# SCH_Project2_2025-11-09.net
KiCad netlist of a schematic drawn in EasyEDA
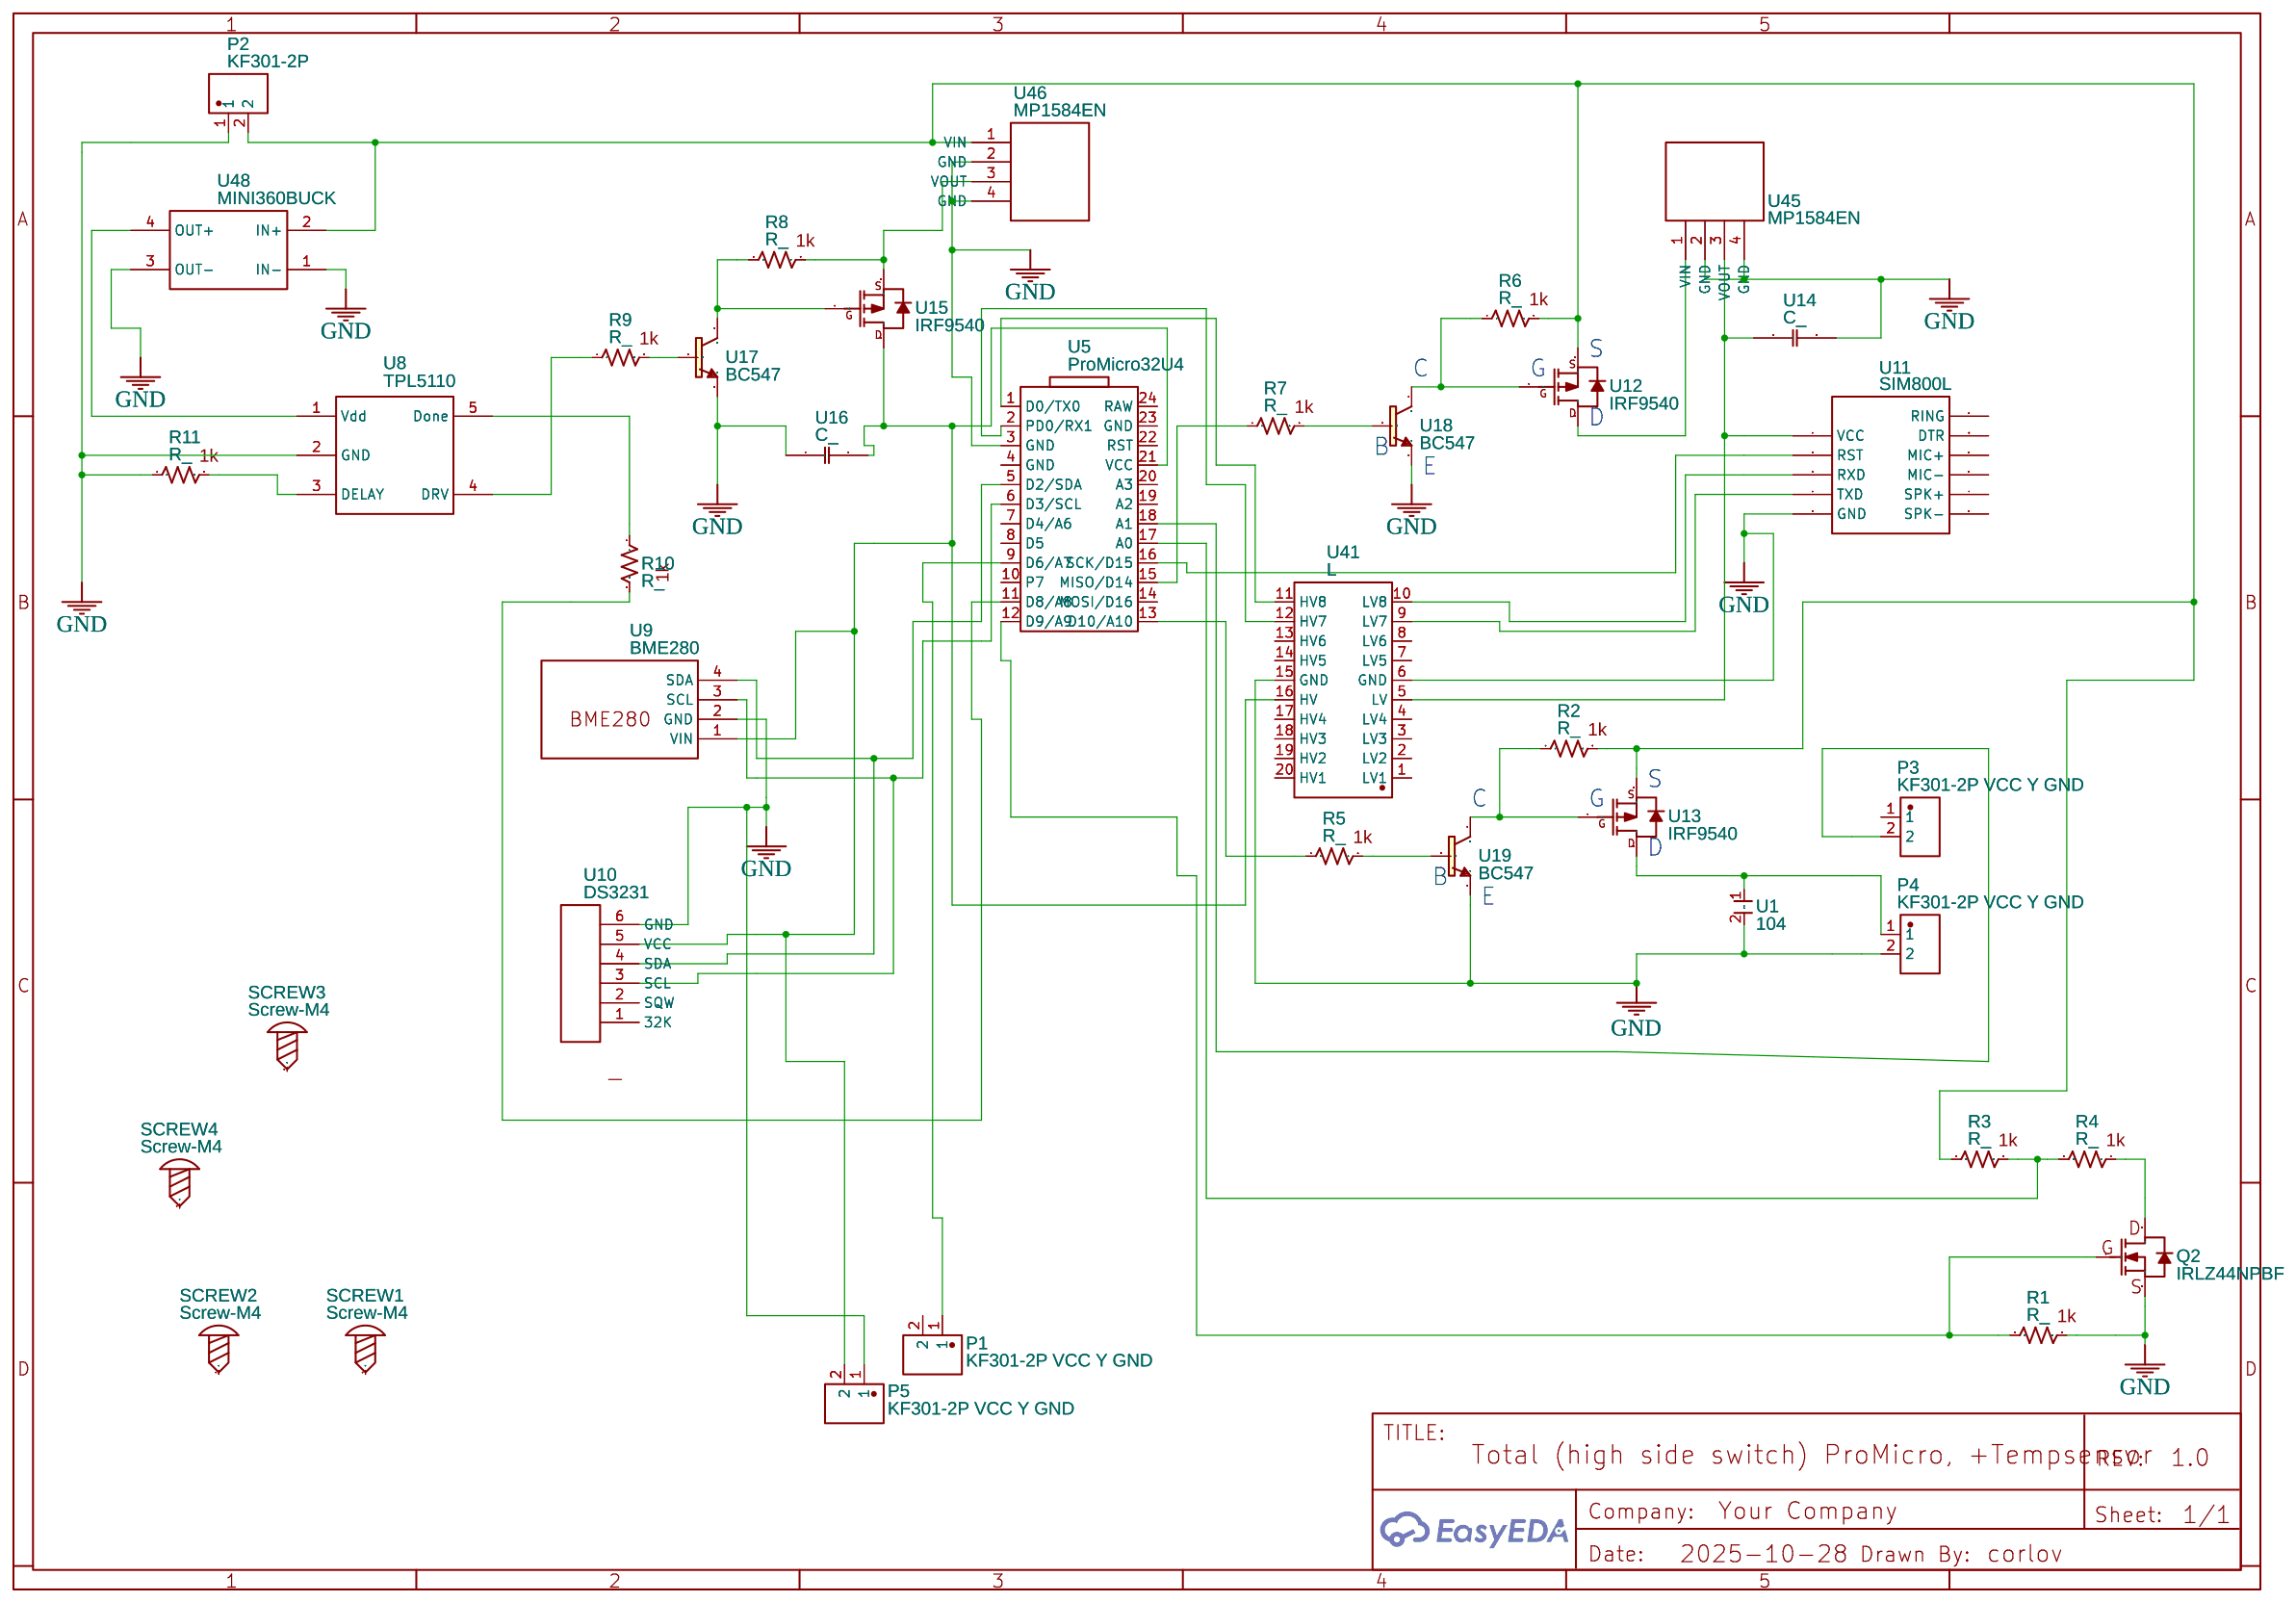
[diagram p0: schematic sheet]

(export (version "E")
  (design (tool "Eeschema 10.0.6"))
  (components
    (comp (ref "P1")
      (value "KF301-2P VCC Y GND")
      (fields (field (name "Manufacturer Part") "KF301-2P接线端子"))
      (libsource (lib "") (part "KF301-2P VCC Y GND_1"))
    )
    (comp (ref "P2")
      (value "KF301-2P")
      (fields (field (name "Manufacturer Part") "KF301-2P接线端子"))
      (libsource (lib "") (part "KF301-2P VCC Y GND_2"))
    )
    (comp (ref "P3")
      (value "KF301-2P VCC Y GND")
      (fields (field (name "Manufacturer Part") "KF301-2P接线端子"))
      (libsource (lib "") (part "KF301-2P VCC Y GND"))
    )
    (comp (ref "P4")
      (value "KF301-2P VCC Y GND")
      (fields (field (name "Manufacturer Part") "KF301-2P接线端子"))
      (libsource (lib "") (part "KF301-2P VCC Y GND"))
    )
    (comp (ref "P5")
      (value "KF301-2P VCC Y GND")
      (fields (field (name "Manufacturer Part") "KF301-2P接线端子"))
      (libsource (lib "") (part "KF301-2P VCC Y GND_1"))
    )
    (comp (ref "Q2")
      (value "IRLZ44NPBF")
      (fields (field (name "Manufacturer") "Infineon(英飞凌)"))
      (libsource (lib "") (part "IRLZ44NPBF"))
    )
    (comp (ref "R1") (value "R_") (libsource (lib "") (part "R_")))
    (comp (ref "R2") (value "R_") (libsource (lib "") (part "R_")))
    (comp (ref "R3") (value "R_") (libsource (lib "") (part "R_")))
    (comp (ref "R4") (value "R_") (libsource (lib "") (part "R_")))
    (comp (ref "R5") (value "R_") (libsource (lib "") (part "R_")))
    (comp (ref "R6") (value "R_") (libsource (lib "") (part "R_")))
    (comp (ref "R7") (value "R_") (libsource (lib "") (part "R_")))
    (comp (ref "R8") (value "R_") (libsource (lib "") (part "R_")))
    (comp (ref "R9") (value "R_") (libsource (lib "") (part "R_")))
    (comp (ref "R10") (value "R_") (libsource (lib "") (part "R__1")))
    (comp (ref "R11") (value "R_") (libsource (lib "") (part "R_")))
    (comp (ref "SCREW1") (value "Screw-M4") (libsource (lib "") (part "Screw-M4")))
    (comp (ref "SCREW2") (value "Screw-M4") (libsource (lib "") (part "Screw-M4")))
    (comp (ref "SCREW3") (value "Screw-M4") (libsource (lib "") (part "Screw-M4")))
    (comp (ref "SCREW4") (value "Screw-M4") (libsource (lib "") (part "Screw-M4")))
    (comp (ref "U1")
      (value "104")
      (fields (field (name "Manufacturer") "Fe"))
      (libsource (lib "") (part "104"))
    )
    (comp (ref "U5")
      (value "ProMicro32U4")
      (fields (field (name "Manufacturer Part") "generic"))
      (libsource (lib "") (part "ProMicro32U4"))
    )
    (comp (ref "U8")
      (value "TPL5110")
      (fields (field (name "Manufacturer Part") "3435"))
      (libsource (lib "") (part "ADAFRUIT TPL5110 BREAKOUT"))
    )
    (comp (ref "U9") (value "BME280") (libsource (lib "") (part "BME280")))
    (comp (ref "U10") (value "DS3231") (libsource (lib "") (part "DS3231 upright")))
    (comp (ref "U11") (value "SIM800L") (libsource (lib "") (part "SIM800L")))
    (comp (ref "U12") (value "IRF9540") (libsource (lib "") (part "IRF9540")))
    (comp (ref "U13") (value "IRF9540") (libsource (lib "") (part "IRF9540")))
    (comp (ref "U14") (value "C_") (libsource (lib "") (part "C_")))
    (comp (ref "U15") (value "IRF9540") (libsource (lib "") (part "IRF9540")))
    (comp (ref "U16") (value "C_") (libsource (lib "") (part "C_")))
    (comp (ref "U17") (value "BC547") (libsource (lib "") (part "BC547")))
    (comp (ref "U18") (value "BC547") (libsource (lib "") (part "BC547")))
    (comp (ref "U19") (value "BC547") (libsource (lib "") (part "BC547")))
    (comp (ref "U41")
      (value "L")
      (fields (field (name "Manufacturer Part") "Level Converter 8"))
      (libsource (lib "") (part "LEVEL CONVERTER 8"))
    )
    (comp (ref "U45") (value "MP1584EN") (libsource (lib "") (part "MP1584EN_1")))
    (comp (ref "U46") (value "MP1584EN") (libsource (lib "") (part "MP1584EN")))
    (comp (ref "U48")
      (value "MINI360BUCK")
      (fields (field (name "Manufacturer Part") "Mini360"))
      (libsource (lib "") (part "MINI360BUCK"))
    )
  )
  (nets
    (net (code "1") (name "GND") (class "Default")
      (node (ref "P2") (pin "1") (pinfunction "1_1") (pintype "unspecified"))
      (node (ref "P4") (pin "2") (pinfunction "2_2") (pintype "unspecified"))
      (node (ref "P5") (pin "1") (pinfunction "1_1") (pintype "unspecified"))
      (node (ref "Q2") (pin "3") (pinfunction "S_3") (pintype "unspecified"))
      (node (ref "R1") (pin "2") (pinfunction "2_2") (pintype "unspecified"))
      (node (ref "R11") (pin "1") (pinfunction "1_1") (pintype "unspecified"))
      (node (ref "U1") (pin "2") (pinfunction "2_2") (pintype "unspecified"))
      (node (ref "U10") (pin "6") (pinfunction "GND_6") (pintype "unspecified"))
      (node (ref "U11") (pin "5") (pinfunction "GND_5") (pintype "unspecified"))
      (node (ref "U14") (pin "2") (pinfunction "2_2") (pintype "unspecified"))
      (node (ref "U16") (pin "1") (pinfunction "1_1") (pintype "unspecified"))
      (node (ref "U17") (pin "3") (pinfunction "E_3") (pintype "unspecified"))
      (node (ref "U18") (pin "3") (pinfunction "E_3") (pintype "unspecified"))
      (node (ref "U19") (pin "3") (pinfunction "E_3") (pintype "unspecified"))
      (node (ref "U41") (pin "15") (pinfunction "GND_15") (pintype "unspecified"))
      (node (ref "U41") (pin "6") (pinfunction "GND_6") (pintype "unspecified"))
      (node (ref "U45") (pin "2") (pinfunction "GND_2") (pintype "unspecified"))
      (node (ref "U45") (pin "4") (pinfunction "GND_4") (pintype "unspecified"))
      (node (ref "U46") (pin "2") (pinfunction "GND_2") (pintype "unspecified"))
      (node (ref "U46") (pin "4") (pinfunction "GND_4") (pintype "unspecified"))
      (node (ref "U48") (pin "1") (pinfunction "IN-_1") (pintype "unspecified"))
      (node (ref "U48") (pin "3") (pinfunction "OUT-_3") (pintype "unspecified"))
      (node (ref "U5") (pin "3") (pinfunction "GND_3") (pintype "unspecified"))
      (node (ref "U8") (pin "2") (pinfunction "GND_2") (pintype "unspecified"))
      (node (ref "U9") (pin "2") (pinfunction "GND_2") (pintype "unspecified"))
    )
    (net (code "2") (name "Net-(Q2-D)") (class "Default")
      (node (ref "Q2") (pin "2") (pinfunction "D_2") (pintype "unspecified"))
      (node (ref "R4") (pin "2") (pinfunction "2_2") (pintype "unspecified"))
    )
    (net (code "3") (name "Net-(Q2-G)") (class "Default")
      (node (ref "Q2") (pin "1") (pinfunction "G_1") (pintype "unspecified"))
      (node (ref "R1") (pin "1") (pinfunction "1_1") (pintype "unspecified"))
      (node (ref "U5") (pin "12") (pinfunction "D9/A9_12") (pintype "unspecified"))
    )
    (net (code "4") (name "Net-(U5-A0)") (class "Default")
      (node (ref "R3") (pin "2") (pinfunction "2_2") (pintype "unspecified"))
      (node (ref "R4") (pin "1") (pinfunction "1_1") (pintype "unspecified"))
      (node (ref "U5") (pin "17") (pinfunction "A0_17") (pintype "unspecified"))
    )
    (net (code "5") (name "Net-(U5-A1)") (class "Default")
      (node (ref "P3") (pin "2") (pinfunction "2_2") (pintype "unspecified"))
      (node (ref "U5") (pin "18") (pinfunction "A1_18") (pintype "unspecified"))
    )
    (net (code "6") (name "Net-(U5-D6{slash}A7)") (class "Default")
      (node (ref "P1") (pin "1") (pinfunction "1_1") (pintype "unspecified"))
      (node (ref "U5") (pin "9") (pinfunction "D6/A7_9") (pintype "unspecified"))
    )
    (net (code "7") (name "Net-(U5-D8{slash}A8)") (class "Default")
      (node (ref "R10") (pin "2") (pinfunction "2_2") (pintype "unspecified"))
      (node (ref "U5") (pin "11") (pinfunction "D8/A8_11") (pintype "unspecified"))
    )
    (net (code "8") (name "Net-(U5-D10{slash}A10)") (class "Default")
      (node (ref "R5") (pin "1") (pinfunction "1_1") (pintype "unspecified"))
      (node (ref "U5") (pin "13") (pinfunction "D10/A10_13") (pintype "unspecified"))
    )
    (net (code "9") (name "Net-(U5-MISO{slash}D14)") (class "Default")
      (node (ref "R7") (pin "1") (pinfunction "1_1") (pintype "unspecified"))
      (node (ref "U5") (pin "15") (pinfunction "MISO/D14_15") (pintype "unspecified"))
    )
    (net (code "10") (name "Net-(U8-DELAY)") (class "Default")
      (node (ref "R11") (pin "2") (pinfunction "2_2") (pintype "unspecified"))
      (node (ref "U8") (pin "3") (pinfunction "DELAY_3") (pintype "unspecified"))
    )
    (net (code "11") (name "Net-(U8-DRV)") (class "Default")
      (node (ref "R9") (pin "1") (pinfunction "1_1") (pintype "unspecified"))
      (node (ref "U8") (pin "4") (pinfunction "DRV_4") (pintype "unspecified"))
    )
    (net (code "12") (name "Net-(U8-Done)") (class "Default")
      (node (ref "R10") (pin "1") (pinfunction "1_1") (pintype "unspecified"))
      (node (ref "U8") (pin "5") (pinfunction "Done_5") (pintype "unspecified"))
    )
    (net (code "13") (name "Net-(U10-SCL)") (class "Default")
      (node (ref "U10") (pin "3") (pinfunction "SCL_3") (pintype "unspecified"))
      (node (ref "U5") (pin "6") (pinfunction "D3/SCL_6") (pintype "unspecified"))
      (node (ref "U9") (pin "3") (pinfunction "SCL_3") (pintype "unspecified"))
    )
    (net (code "14") (name "Net-(U10-SDA)") (class "Default")
      (node (ref "U10") (pin "4") (pinfunction "SDA_4") (pintype "unspecified"))
      (node (ref "U5") (pin "5") (pinfunction "D2/SDA_5") (pintype "unspecified"))
      (node (ref "U9") (pin "4") (pinfunction "SDA_4") (pintype "unspecified"))
    )
    (net (code "15") (name "Net-(U10-VCC)") (class "Default")
      (node (ref "P5") (pin "2") (pinfunction "2_2") (pintype "unspecified"))
      (node (ref "U10") (pin "5") (pinfunction "VCC_5") (pintype "unspecified"))
      (node (ref "U15") (pin "2") (pinfunction "D_2") (pintype "unspecified"))
      (node (ref "U16") (pin "2") (pinfunction "2_2") (pintype "unspecified"))
      (node (ref "U41") (pin "16") (pinfunction "HV_16") (pintype "unspecified"))
      (node (ref "U5") (pin "21") (pinfunction "VCC_21") (pintype "unspecified"))
      (node (ref "U9") (pin "1") (pinfunction "VIN_1") (pintype "unspecified"))
    )
    (net (code "16") (name "Net-(U11-RST)") (class "Default")
      (node (ref "U11") (pin "2") (pinfunction "RST_2") (pintype "unspecified"))
      (node (ref "U5") (pin "16") (pinfunction "SCK/D15_16") (pintype "unspecified"))
    )
    (net (code "17") (name "Net-(U11-RXD)") (class "Default")
      (node (ref "U11") (pin "3") (pinfunction "RXD_3") (pintype "unspecified"))
      (node (ref "U41") (pin "10") (pinfunction "LV8_10") (pintype "unspecified"))
    )
    (net (code "18") (name "Net-(U11-TXD)") (class "Default")
      (node (ref "U11") (pin "4") (pinfunction "TXD_4") (pintype "unspecified"))
      (node (ref "U41") (pin "9") (pinfunction "LV7_9") (pintype "unspecified"))
    )
    (net (code "19") (name "Net-(U11-VCC)") (class "Default")
      (node (ref "U11") (pin "1") (pinfunction "VCC_1") (pintype "unspecified"))
      (node (ref "U14") (pin "1") (pinfunction "1_1") (pintype "unspecified"))
      (node (ref "U41") (pin "5") (pinfunction "LV_5") (pintype "unspecified"))
      (node (ref "U45") (pin "3") (pinfunction "VOUT_3") (pintype "unspecified"))
    )
    (net (code "20") (name "Net-(U12-D)") (class "Default")
      (node (ref "U12") (pin "2") (pinfunction "D_2") (pintype "unspecified"))
      (node (ref "U45") (pin "1") (pinfunction "VIN_1") (pintype "unspecified"))
    )
    (net (code "21") (name "Net-(U12-G)") (class "Default")
      (node (ref "R6") (pin "1") (pinfunction "1_1") (pintype "unspecified"))
      (node (ref "U12") (pin "1") (pinfunction "G_1") (pintype "unspecified"))
      (node (ref "U18") (pin "1") (pinfunction "C_1") (pintype "unspecified"))
    )
    (net (code "22") (name "Net-(U12-S)") (class "Default")
      (node (ref "P2") (pin "2") (pinfunction "2_2") (pintype "unspecified"))
      (node (ref "R2") (pin "2") (pinfunction "2_2") (pintype "unspecified"))
      (node (ref "R3") (pin "1") (pinfunction "1_1") (pintype "unspecified"))
      (node (ref "R6") (pin "2") (pinfunction "2_2") (pintype "unspecified"))
      (node (ref "U12") (pin "3") (pinfunction "S_3") (pintype "unspecified"))
      (node (ref "U13") (pin "3") (pinfunction "S_3") (pintype "unspecified"))
      (node (ref "U46") (pin "1") (pinfunction "VIN_1") (pintype "unspecified"))
      (node (ref "U48") (pin "2") (pinfunction "IN+_2") (pintype "unspecified"))
    )
    (net (code "23") (name "Net-(U13-D)") (class "Default")
      (node (ref "P4") (pin "1") (pinfunction "1_1") (pintype "unspecified"))
      (node (ref "U1") (pin "1") (pinfunction "1_1") (pintype "unspecified"))
      (node (ref "U13") (pin "2") (pinfunction "D_2") (pintype "unspecified"))
    )
    (net (code "24") (name "Net-(U13-G)") (class "Default")
      (node (ref "R2") (pin "1") (pinfunction "1_1") (pintype "unspecified"))
      (node (ref "U13") (pin "1") (pinfunction "G_1") (pintype "unspecified"))
      (node (ref "U19") (pin "1") (pinfunction "C_1") (pintype "unspecified"))
    )
    (net (code "25") (name "Net-(U15-G)") (class "Default")
      (node (ref "R8") (pin "1") (pinfunction "1_1") (pintype "unspecified"))
      (node (ref "U15") (pin "1") (pinfunction "G_1") (pintype "unspecified"))
      (node (ref "U17") (pin "1") (pinfunction "C_1") (pintype "unspecified"))
    )
    (net (code "26") (name "Net-(U15-S)") (class "Default")
      (node (ref "R8") (pin "2") (pinfunction "2_2") (pintype "unspecified"))
      (node (ref "U15") (pin "3") (pinfunction "S_3") (pintype "unspecified"))
      (node (ref "U46") (pin "3") (pinfunction "VOUT_3") (pintype "unspecified"))
    )
    (net (code "27") (name "Net-(U17-B)") (class "Default")
      (node (ref "R9") (pin "2") (pinfunction "2_2") (pintype "unspecified"))
      (node (ref "U17") (pin "2") (pinfunction "B_2") (pintype "unspecified"))
    )
    (net (code "28") (name "Net-(U18-B)") (class "Default")
      (node (ref "R7") (pin "2") (pinfunction "2_2") (pintype "unspecified"))
      (node (ref "U18") (pin "2") (pinfunction "B_2") (pintype "unspecified"))
    )
    (net (code "29") (name "Net-(U19-B)") (class "Default")
      (node (ref "R5") (pin "2") (pinfunction "2_2") (pintype "unspecified"))
      (node (ref "U19") (pin "2") (pinfunction "B_2") (pintype "unspecified"))
    )
    (net (code "30") (name "Net-(U41-HV7)") (class "Default")
      (node (ref "U41") (pin "12") (pinfunction "HV7_12") (pintype "unspecified"))
      (node (ref "U5") (pin "2") (pinfunction "PD0/RX1_2") (pintype "unspecified"))
    )
    (net (code "31") (name "Net-(U41-HV8)") (class "Default")
      (node (ref "U41") (pin "11") (pinfunction "HV8_11") (pintype "unspecified"))
      (node (ref "U5") (pin "1") (pinfunction "D0/TX0_1") (pintype "unspecified"))
    )
    (net (code "32") (name "Net-(U48-OUT+)") (class "Default")
      (node (ref "U48") (pin "4") (pinfunction "OUT+_4") (pintype "unspecified"))
      (node (ref "U8") (pin "1") (pinfunction "Vdd_1") (pintype "unspecified"))
    )
    (net (code "33") (name "unconnected-(P1-Pad2)") (class "Default")
      (node (ref "P1") (pin "2") (pinfunction "2_2") (pintype "unspecified"))
    )
    (net (code "34") (name "unconnected-(P3-Pad1)") (class "Default")
      (node (ref "P3") (pin "1") (pinfunction "1_1") (pintype "unspecified"))
    )
    (net (code "35") (name "unconnected-(SCREW1-Pad1)") (class "Default")
      (node (ref "SCREW1") (pin "1") (pinfunction "1_1") (pintype "unspecified"))
    )
    (net (code "36") (name "unconnected-(SCREW2-Pad1)") (class "Default")
      (node (ref "SCREW2") (pin "1") (pinfunction "1_1") (pintype "unspecified"))
    )
    (net (code "37") (name "unconnected-(SCREW3-Pad1)") (class "Default")
      (node (ref "SCREW3") (pin "1") (pinfunction "1_1") (pintype "unspecified"))
    )
    (net (code "38") (name "unconnected-(SCREW4-Pad1)") (class "Default")
      (node (ref "SCREW4") (pin "1") (pinfunction "1_1") (pintype "unspecified"))
    )
    (net (code "39") (name "unconnected-(U5-A2-Pad19)") (class "Default")
      (node (ref "U5") (pin "19") (pinfunction "A2_19") (pintype "unspecified"))
    )
    (net (code "40") (name "unconnected-(U5-A3-Pad20)") (class "Default")
      (node (ref "U5") (pin "20") (pinfunction "A3_20") (pintype "unspecified"))
    )
    (net (code "41") (name "unconnected-(U5-D4{slash}A6-Pad7)") (class "Default")
      (node (ref "U5") (pin "7") (pinfunction "D4/A6_7") (pintype "unspecified"))
    )
    (net (code "42") (name "unconnected-(U5-D5-Pad8)") (class "Default")
      (node (ref "U5") (pin "8") (pinfunction "D5_8") (pintype "unspecified"))
    )
    (net (code "43") (name "unconnected-(U5-GND-Pad4)") (class "Default")
      (node (ref "U5") (pin "4") (pinfunction "GND_4") (pintype "unspecified"))
    )
    (net (code "44") (name "unconnected-(U5-GND-Pad23)") (class "Default")
      (node (ref "U5") (pin "23") (pinfunction "GND_23") (pintype "unspecified"))
    )
    (net (code "45") (name "unconnected-(U5-MOSI{slash}D16-Pad14)") (class "Default")
      (node (ref "U5") (pin "14") (pinfunction "MOSI/D16_14") (pintype "unspecified"))
    )
    (net (code "46") (name "unconnected-(U5-P7-Pad10)") (class "Default")
      (node (ref "U5") (pin "10") (pinfunction "P7_10") (pintype "unspecified"))
    )
    (net (code "47") (name "unconnected-(U5-RAW-Pad24)") (class "Default")
      (node (ref "U5") (pin "24") (pinfunction "RAW_24") (pintype "unspecified"))
    )
    (net (code "48") (name "unconnected-(U5-RST-Pad22)") (class "Default")
      (node (ref "U5") (pin "22") (pinfunction "RST_22") (pintype "unspecified"))
    )
    (net (code "49") (name "unconnected-(U10-32K-Pad1)") (class "Default")
      (node (ref "U10") (pin "1") (pinfunction "32K_1") (pintype "unspecified"))
    )
    (net (code "50") (name "unconnected-(U10-SQW-Pad2)") (class "Default")
      (node (ref "U10") (pin "2") (pinfunction "SQW_2") (pintype "unspecified"))
    )
    (net (code "51") (name "unconnected-(U11-DTR-Pad10)") (class "Default")
      (node (ref "U11") (pin "10") (pinfunction "DTR_10") (pintype "unspecified"))
    )
    (net (code "52") (name "unconnected-(U11-MIC+-Pad9)") (class "Default")
      (node (ref "U11") (pin "9") (pinfunction "MIC+_9") (pintype "unspecified"))
    )
    (net (code "53") (name "unconnected-(U11-MIC--Pad8)") (class "Default")
      (node (ref "U11") (pin "8") (pinfunction "MIC-_8") (pintype "unspecified"))
    )
    (net (code "54") (name "unconnected-(U11-RING-Pad11)") (class "Default")
      (node (ref "U11") (pin "11") (pinfunction "RING_11") (pintype "unspecified"))
    )
    (net (code "55") (name "unconnected-(U11-SPK+-Pad7)") (class "Default")
      (node (ref "U11") (pin "7") (pinfunction "SPK+_7") (pintype "unspecified"))
    )
    (net (code "56") (name "unconnected-(U11-SPK--Pad6)") (class "Default")
      (node (ref "U11") (pin "6") (pinfunction "SPK-_6") (pintype "unspecified"))
    )
    (net (code "57") (name "unconnected-(U41-HV1-Pad20)") (class "Default")
      (node (ref "U41") (pin "20") (pinfunction "HV1_20") (pintype "unspecified"))
    )
    (net (code "58") (name "unconnected-(U41-HV2-Pad19)") (class "Default")
      (node (ref "U41") (pin "19") (pinfunction "HV2_19") (pintype "unspecified"))
    )
    (net (code "59") (name "unconnected-(U41-HV3-Pad18)") (class "Default")
      (node (ref "U41") (pin "18") (pinfunction "HV3_18") (pintype "unspecified"))
    )
    (net (code "60") (name "unconnected-(U41-HV4-Pad17)") (class "Default")
      (node (ref "U41") (pin "17") (pinfunction "HV4_17") (pintype "unspecified"))
    )
    (net (code "61") (name "unconnected-(U41-HV5-Pad14)") (class "Default")
      (node (ref "U41") (pin "14") (pinfunction "HV5_14") (pintype "unspecified"))
    )
    (net (code "62") (name "unconnected-(U41-HV6-Pad13)") (class "Default")
      (node (ref "U41") (pin "13") (pinfunction "HV6_13") (pintype "unspecified"))
    )
    (net (code "63") (name "unconnected-(U41-LV1-Pad1)") (class "Default")
      (node (ref "U41") (pin "1") (pinfunction "LV1_1") (pintype "unspecified"))
    )
    (net (code "64") (name "unconnected-(U41-LV2-Pad2)") (class "Default")
      (node (ref "U41") (pin "2") (pinfunction "LV2_2") (pintype "unspecified"))
    )
    (net (code "65") (name "unconnected-(U41-LV3-Pad3)") (class "Default")
      (node (ref "U41") (pin "3") (pinfunction "LV3_3") (pintype "unspecified"))
    )
    (net (code "66") (name "unconnected-(U41-LV4-Pad4)") (class "Default")
      (node (ref "U41") (pin "4") (pinfunction "LV4_4") (pintype "unspecified"))
    )
    (net (code "67") (name "unconnected-(U41-LV5-Pad7)") (class "Default")
      (node (ref "U41") (pin "7") (pinfunction "LV5_7") (pintype "unspecified"))
    )
    (net (code "68") (name "unconnected-(U41-LV6-Pad8)") (class "Default")
      (node (ref "U41") (pin "8") (pinfunction "LV6_8") (pintype "unspecified"))
    )
  )
)
